# lpc134x.net
KiCad netlist of a schematic drawn in EAGLE
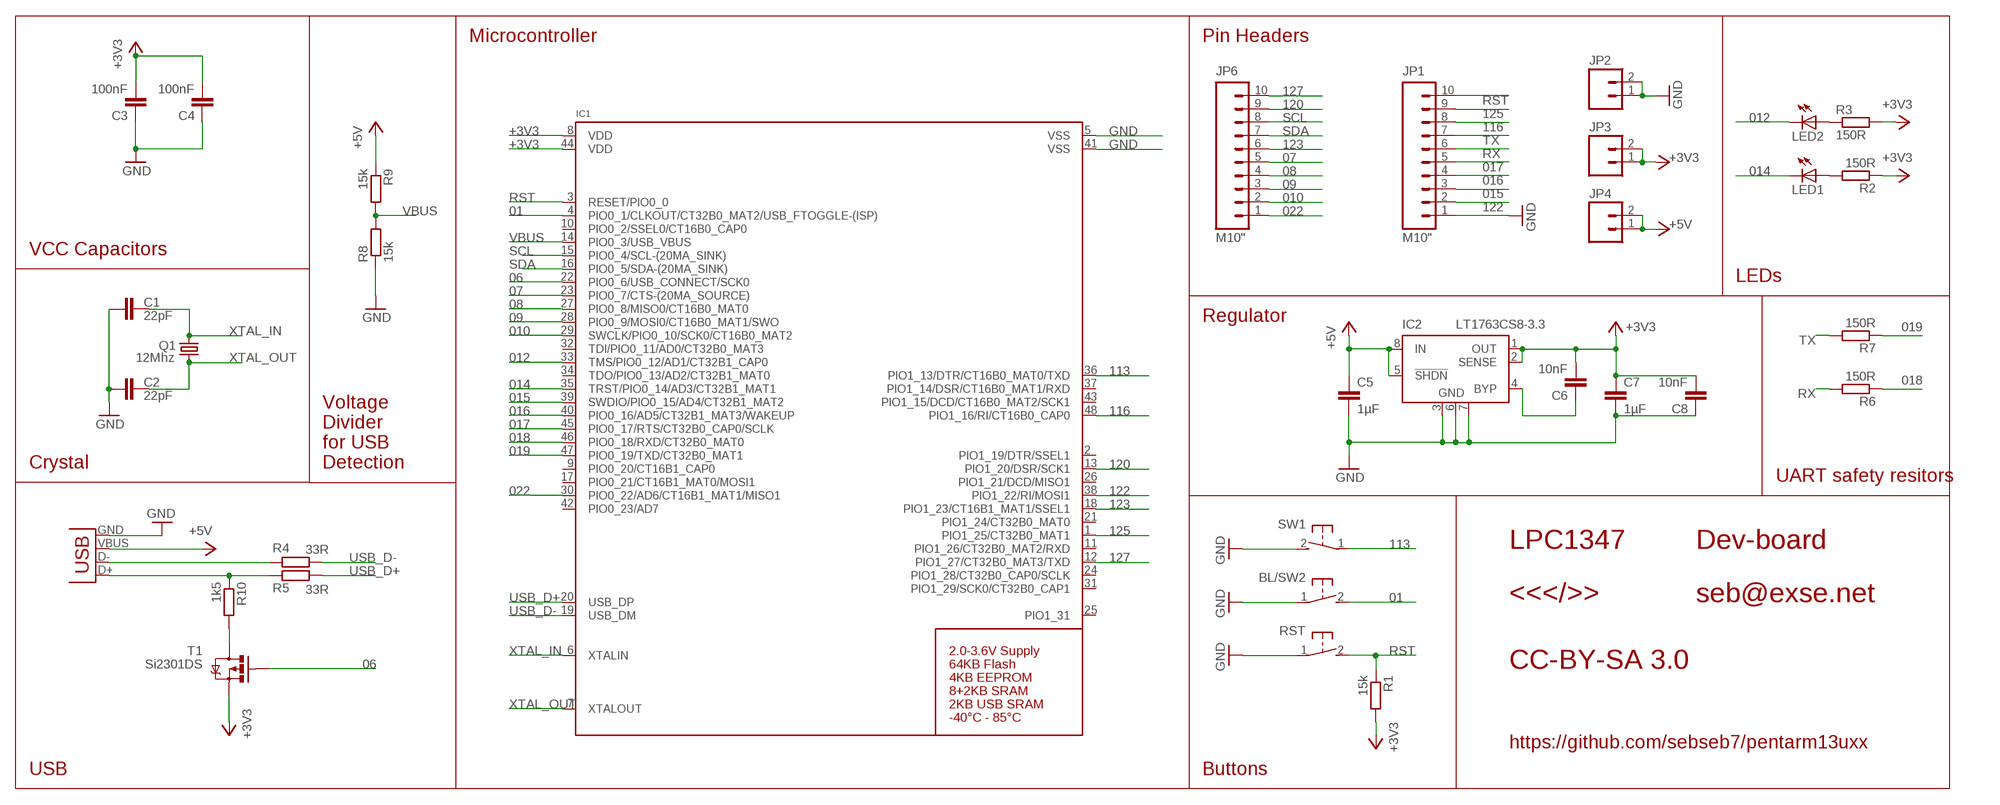
[diagram p0: schematic, sheet 1]

(export (version "E")
  (design (tool "Eeschema 10.0.6"))
  (components
    (comp (ref "BL/SW2")
      (value "SWITCH_MCTAEF")
      (footprint "eagle-import:SWITCH_MCTAEF")
      (libsource (lib "eagle-import") (part "SWITCH_MCTAEF"))
    )
    (comp (ref "C1")
      (value "22pF")
      (footprint "eagle-import:C0402")
      (libsource (lib "eagle-import") (part "C-EUC0402"))
    )
    (comp (ref "C2")
      (value "22pF")
      (footprint "eagle-import:C0402")
      (libsource (lib "eagle-import") (part "C-EUC0402"))
    )
    (comp (ref "C3")
      (value "100nF")
      (footprint "eagle-import:C0402")
      (libsource (lib "eagle-import") (part "C-EUC0402"))
    )
    (comp (ref "C4")
      (value "100nF")
      (footprint "eagle-import:C0402")
      (libsource (lib "eagle-import") (part "C-EUC0402"))
    )
    (comp (ref "C5")
      (value "1µF")
      (footprint "eagle-import:0805")
      (libsource (lib "eagle-import") (part "CAP0805"))
    )
    (comp (ref "C6")
      (value "10nF")
      (footprint "eagle-import:C0402")
      (libsource (lib "eagle-import") (part "C-EUC0402"))
    )
    (comp (ref "C7")
      (value "1µF")
      (footprint "eagle-import:0805")
      (libsource (lib "eagle-import") (part "CAP0805"))
    )
    (comp (ref "C8")
      (value "10nF")
      (footprint "eagle-import:C0402")
      (libsource (lib "eagle-import") (part "C-EUC0402"))
    )
    (comp (ref "IC1")
      (value "LPC1347_QFP48")
      (footprint "eagle-import:LQFP48")
      (libsource (lib "eagle-import") (part "LPC1347_QFP48"))
    )
    (comp (ref "IC2")
      (value "LT1763CS8-3.3")
      (footprint "eagle-import:SOIC8")
      (libsource (lib "eagle-import") (part "LT1763CS8-3.3"))
    )
    (comp (ref "JP1")
      (value "M10\"")
      (footprint "eagle-import:1X10")
      (libsource (lib "eagle-import") (part "M10{dblquote}"))
    )
    (comp (ref "JP2")
      (value "M02PTH")
      (footprint "eagle-import:1X02")
      (libsource (lib "eagle-import") (part "M02PTH"))
    )
    (comp (ref "JP3")
      (value "M02PTH")
      (footprint "eagle-import:1X02")
      (libsource (lib "eagle-import") (part "M02PTH"))
    )
    (comp (ref "JP4")
      (value "M02PTH")
      (footprint "eagle-import:1X02")
      (libsource (lib "eagle-import") (part "M02PTH"))
    )
    (comp (ref "JP6")
      (value "M10\"")
      (footprint "eagle-import:1X10")
      (libsource (lib "eagle-import") (part "M10{dblquote}"))
    )
    (comp (ref "LED1")
      (value "LEDCHIPLED_0805")
      (footprint "eagle-import:CHIPLED_0805")
      (libsource (lib "eagle-import") (part "LEDCHIPLED_0805"))
    )
    (comp (ref "LED2")
      (value "LEDCHIPLED_0805")
      (footprint "eagle-import:CHIPLED_0805")
      (libsource (lib "eagle-import") (part "LEDCHIPLED_0805"))
    )
    (comp (ref "Q1")
      (value "12Mhz")
      (footprint "eagle-import:MT")
      (libsource (lib "eagle-import") (part "MT-OSCILLATOR"))
    )
    (comp (ref "R1")
      (value "15k")
      (footprint "eagle-import:R0402")
      (libsource (lib "eagle-import") (part "R-EU_R0402"))
    )
    (comp (ref "R2")
      (value "150R")
      (footprint "eagle-import:R0402")
      (libsource (lib "eagle-import") (part "R-EU_R0402"))
    )
    (comp (ref "R3")
      (value "150R")
      (footprint "eagle-import:R0402")
      (libsource (lib "eagle-import") (part "R-EU_R0402"))
    )
    (comp (ref "R4")
      (value "33R")
      (footprint "eagle-import:R0402")
      (libsource (lib "eagle-import") (part "R-EU_R0402"))
    )
    (comp (ref "R5")
      (value "33R")
      (footprint "eagle-import:R0402")
      (libsource (lib "eagle-import") (part "R-EU_R0402"))
    )
    (comp (ref "R6")
      (value "150R")
      (footprint "eagle-import:R0402")
      (libsource (lib "eagle-import") (part "R-EU_R0402"))
    )
    (comp (ref "R7")
      (value "150R")
      (footprint "eagle-import:R0402")
      (libsource (lib "eagle-import") (part "R-EU_R0402"))
    )
    (comp (ref "R8")
      (value "15k")
      (footprint "eagle-import:R0402")
      (libsource (lib "eagle-import") (part "R-EU_R0402"))
    )
    (comp (ref "R9")
      (value "15k")
      (footprint "eagle-import:R0402")
      (libsource (lib "eagle-import") (part "R-EU_R0402"))
    )
    (comp (ref "R10")
      (value "1k5")
      (footprint "eagle-import:R0402")
      (libsource (lib "eagle-import") (part "R-EU_R0402"))
    )
    (comp (ref "RST")
      (value "SWITCH_MCTAEF")
      (footprint "eagle-import:SWITCH_MCTAEF")
      (libsource (lib "eagle-import") (part "SWITCH_MCTAEF"))
    )
    (comp (ref "SW1")
      (value "SWITCH_MCTAEF")
      (footprint "eagle-import:SWITCH_MCTAEF")
      (libsource (lib "eagle-import") (part "SWITCH_MCTAEF"))
    )
    (comp (ref "T1")
      (value "Si2301DS")
      (footprint "eagle-import:SOT23")
      (libsource (lib "eagle-import") (part "MOSFET-PCHANNEL"))
    )
    (comp (ref "X2")
      (value "USB-SMD-NS")
      (footprint "eagle-import:USB-MINIB-NOSTOP")
      (libsource (lib "eagle-import") (part "USB-SMD-NS"))
    )
  )
  (nets
    (net (code "1") (name "+3V3") (class "Default")
      (node (ref "C3") (pin "2") (pinfunction "2_2") (pintype "passive"))
      (node (ref "C4") (pin "2") (pinfunction "2_2") (pintype "passive"))
      (node (ref "C6") (pin "2") (pinfunction "2_2") (pintype "passive"))
      (node (ref "C7") (pin "1") (pinfunction "1_1") (pintype "passive"))
      (node (ref "C8") (pin "2") (pinfunction "2_2") (pintype "passive"))
      (node (ref "IC1") (pin "44") (pinfunction "VDD_44") (pintype "power_in"))
      (node (ref "IC1") (pin "8") (pinfunction "VDD_8") (pintype "power_in"))
      (node (ref "IC2") (pin "1") (pinfunction "OUT_1") (pintype "passive"))
      (node (ref "IC2") (pin "2") (pinfunction "SENSE_2") (pintype "input"))
      (node (ref "JP3") (pin "1") (pinfunction "1_1") (pintype "passive"))
      (node (ref "JP3") (pin "2") (pinfunction "2_2") (pintype "passive"))
      (node (ref "R1") (pin "2") (pinfunction "2_2") (pintype "passive"))
      (node (ref "R2") (pin "1") (pinfunction "1_1") (pintype "passive"))
      (node (ref "R3") (pin "2") (pinfunction "2_2") (pintype "passive"))
      (node (ref "T1") (pin "2") (pinfunction "S_2") (pintype "passive"))
    )
    (net (code "2") (name "+5V") (class "Default")
      (node (ref "C5") (pin "1") (pinfunction "1_1") (pintype "passive"))
      (node (ref "IC2") (pin "5") (pinfunction "~{SHDN}_5") (pintype "input"))
      (node (ref "IC2") (pin "8") (pinfunction "IN_8") (pintype "input"))
      (node (ref "JP4") (pin "1") (pinfunction "1_1") (pintype "passive"))
      (node (ref "JP4") (pin "2") (pinfunction "2_2") (pintype "passive"))
      (node (ref "R9") (pin "1") (pinfunction "1_1") (pintype "passive"))
      (node (ref "X2") (pin "VBUS") (pinfunction "VBUS_VBUS") (pintype "bidirectional"))
    )
    (net (code "3") (name "/01") (class "Default")
      (node (ref "BL/SW2") (pin "2") (pinfunction "2_2") (pintype "passive"))
      (node (ref "IC1") (pin "4") (pinfunction "PIO0_1/CLKOUT/CT32B0_MAT2/USB_FTOGGLE-(ISP)_4") (pintype "bidirectional"))
    )
    (net (code "4") (name "/06") (class "Default")
      (node (ref "IC1") (pin "22") (pinfunction "PIO0_6/USB_CONNECT/SCK0_22") (pintype "bidirectional"))
      (node (ref "T1") (pin "1") (pinfunction "G_1") (pintype "passive"))
    )
    (net (code "5") (name "/07") (class "Default")
      (node (ref "IC1") (pin "23") (pinfunction "PIO0_7/CTS-(20MA_SOURCE)_23") (pintype "bidirectional"))
      (node (ref "JP6") (pin "5") (pinfunction "5_5") (pintype "passive"))
    )
    (net (code "6") (name "/08") (class "Default")
      (node (ref "IC1") (pin "27") (pinfunction "PIO0_8/MISO0/CT16B0_MAT0_27") (pintype "bidirectional"))
      (node (ref "JP6") (pin "4") (pinfunction "4_4") (pintype "passive"))
    )
    (net (code "7") (name "/09") (class "Default")
      (node (ref "IC1") (pin "28") (pinfunction "PIO0_9/MOSI0/CT16B0_MAT1/SWO_28") (pintype "bidirectional"))
      (node (ref "JP6") (pin "3") (pinfunction "3_3") (pintype "passive"))
    )
    (net (code "8") (name "/010") (class "Default")
      (node (ref "IC1") (pin "29") (pinfunction "SWCLK/PIO0_10/SCK0/CT16B0_MAT2_29") (pintype "bidirectional"))
      (node (ref "JP6") (pin "2") (pinfunction "2_2") (pintype "passive"))
    )
    (net (code "9") (name "/012") (class "Default")
      (node (ref "IC1") (pin "33") (pinfunction "TMS/PIO0_12/AD1/CT32B1_CAP0_33") (pintype "bidirectional"))
      (node (ref "LED2") (pin "C") (pinfunction "C_C") (pintype "passive"))
    )
    (net (code "10") (name "/014") (class "Default")
      (node (ref "IC1") (pin "35") (pinfunction "TRST/PIO0_14/AD3/CT32B1_MAT1_35") (pintype "bidirectional"))
      (node (ref "LED1") (pin "C") (pinfunction "C_C") (pintype "passive"))
    )
    (net (code "11") (name "/015") (class "Default")
      (node (ref "IC1") (pin "39") (pinfunction "SWDIO/PIO0_15/AD4/CT32B1_MAT2_39") (pintype "bidirectional"))
      (node (ref "JP1") (pin "3") (pinfunction "3_3") (pintype "passive"))
    )
    (net (code "12") (name "/016") (class "Default")
      (node (ref "IC1") (pin "40") (pinfunction "PIO0_16/AD5/CT32B1_MAT3/WAKEUP_40") (pintype "bidirectional"))
      (node (ref "JP1") (pin "4") (pinfunction "4_4") (pintype "passive"))
    )
    (net (code "13") (name "/017") (class "Default")
      (node (ref "IC1") (pin "45") (pinfunction "PIO0_17/RTS/CT32B0_CAP0/SCLK_45") (pintype "bidirectional"))
      (node (ref "JP1") (pin "5") (pinfunction "5_5") (pintype "passive"))
    )
    (net (code "14") (name "/018") (class "Default")
      (node (ref "IC1") (pin "46") (pinfunction "PIO0_18/RXD/CT32B0_MAT0_46") (pintype "bidirectional"))
      (node (ref "R6") (pin "1") (pinfunction "1_1") (pintype "passive"))
    )
    (net (code "15") (name "/019") (class "Default")
      (node (ref "IC1") (pin "47") (pinfunction "PIO0_19/TXD/CT32B0_MAT1_47") (pintype "bidirectional"))
      (node (ref "R7") (pin "1") (pinfunction "1_1") (pintype "passive"))
    )
    (net (code "16") (name "/022") (class "Default")
      (node (ref "IC1") (pin "30") (pinfunction "PIO0_22/AD6/CT16B1_MAT1/MISO1_30") (pintype "bidirectional"))
      (node (ref "JP6") (pin "1") (pinfunction "1_1") (pintype "passive"))
    )
    (net (code "17") (name "/113") (class "Default")
      (node (ref "IC1") (pin "36") (pinfunction "PIO1_13/DTR/CT16B0_MAT0/TXD_36") (pintype "bidirectional"))
      (node (ref "SW1") (pin "1") (pinfunction "1_1") (pintype "passive"))
    )
    (net (code "18") (name "/116") (class "Default")
      (node (ref "IC1") (pin "48") (pinfunction "PIO1_16/RI/CT16B0_CAP0_48") (pintype "bidirectional"))
      (node (ref "JP1") (pin "8") (pinfunction "8_8") (pintype "passive"))
    )
    (net (code "19") (name "/120") (class "Default")
      (node (ref "IC1") (pin "13") (pinfunction "PIO1_20/DSR/SCK1_13") (pintype "bidirectional"))
      (node (ref "JP6") (pin "9") (pinfunction "9_9") (pintype "passive"))
    )
    (net (code "20") (name "/122") (class "Default")
      (node (ref "IC1") (pin "38") (pinfunction "PIO1_22/RI/MOSI1_38") (pintype "bidirectional"))
      (node (ref "JP1") (pin "2") (pinfunction "2_2") (pintype "passive"))
    )
    (net (code "21") (name "/123") (class "Default")
      (node (ref "IC1") (pin "18") (pinfunction "PIO1_23/CT16B1_MAT1/SSEL1_18") (pintype "bidirectional"))
      (node (ref "JP6") (pin "6") (pinfunction "6_6") (pintype "passive"))
    )
    (net (code "22") (name "/125") (class "Default")
      (node (ref "IC1") (pin "1") (pinfunction "PIO1_25/CT32B0_MAT1_1") (pintype "bidirectional"))
      (node (ref "JP1") (pin "9") (pinfunction "9_9") (pintype "passive"))
    )
    (net (code "23") (name "/127") (class "Default")
      (node (ref "IC1") (pin "12") (pinfunction "PIO1_27/CT32B0_MAT3/TXD_12") (pintype "bidirectional"))
      (node (ref "JP6") (pin "10") (pinfunction "10_10") (pintype "passive"))
    )
    (net (code "24") (name "/RST") (class "Default")
      (node (ref "IC1") (pin "3") (pinfunction "RESET/PIO0_0_3") (pintype "bidirectional"))
      (node (ref "JP1") (pin "10") (pinfunction "10_10") (pintype "passive"))
      (node (ref "R1") (pin "1") (pinfunction "1_1") (pintype "passive"))
      (node (ref "RST") (pin "2") (pinfunction "2_2") (pintype "passive"))
    )
    (net (code "25") (name "/RX") (class "Default")
      (node (ref "JP1") (pin "6") (pinfunction "6_6") (pintype "passive"))
      (node (ref "R6") (pin "2") (pinfunction "2_2") (pintype "passive"))
    )
    (net (code "26") (name "/SCL") (class "Default")
      (node (ref "IC1") (pin "15") (pinfunction "PIO0_4/SCL-(20MA_SINK)_15") (pintype "bidirectional"))
      (node (ref "JP6") (pin "8") (pinfunction "8_8") (pintype "passive"))
    )
    (net (code "27") (name "/SDA") (class "Default")
      (node (ref "IC1") (pin "16") (pinfunction "PIO0_5/SDA-(20MA_SINK)_16") (pintype "bidirectional"))
      (node (ref "JP6") (pin "7") (pinfunction "7_7") (pintype "passive"))
    )
    (net (code "28") (name "/TX") (class "Default")
      (node (ref "JP1") (pin "7") (pinfunction "7_7") (pintype "passive"))
      (node (ref "R7") (pin "2") (pinfunction "2_2") (pintype "passive"))
    )
    (net (code "29") (name "/USB_D+") (class "Default")
      (node (ref "IC1") (pin "20") (pinfunction "USB_DP_20") (pintype "bidirectional"))
      (node (ref "R5") (pin "1") (pinfunction "1_1") (pintype "passive"))
    )
    (net (code "30") (name "/USB_D-") (class "Default")
      (node (ref "IC1") (pin "19") (pinfunction "USB_DM_19") (pintype "bidirectional"))
      (node (ref "R4") (pin "1") (pinfunction "1_1") (pintype "passive"))
    )
    (net (code "31") (name "/VBUS") (class "Default")
      (node (ref "IC1") (pin "14") (pinfunction "PIO0_3/USB_VBUS_14") (pintype "bidirectional"))
      (node (ref "R8") (pin "2") (pinfunction "2_2") (pintype "passive"))
      (node (ref "R9") (pin "2") (pinfunction "2_2") (pintype "passive"))
    )
    (net (code "32") (name "/XTAL_IN") (class "Default")
      (node (ref "C1") (pin "2") (pinfunction "2_2") (pintype "passive"))
      (node (ref "IC1") (pin "6") (pinfunction "XTALIN_6") (pintype "bidirectional"))
      (node (ref "Q1") (pin "3") (pinfunction "2_3") (pintype "passive"))
    )
    (net (code "33") (name "/XTAL_OUT") (class "Default")
      (node (ref "C2") (pin "2") (pinfunction "2_2") (pintype "passive"))
      (node (ref "IC1") (pin "7") (pinfunction "XTALOUT_7") (pintype "bidirectional"))
      (node (ref "Q1") (pin "1") (pinfunction "1_1") (pintype "passive"))
    )
    (net (code "34") (name "GND") (class "Default")
      (node (ref "BL/SW2") (pin "1") (pinfunction "1_1") (pintype "passive"))
      (node (ref "C1") (pin "1") (pinfunction "1_1") (pintype "passive"))
      (node (ref "C2") (pin "1") (pinfunction "1_1") (pintype "passive"))
      (node (ref "C3") (pin "1") (pinfunction "1_1") (pintype "passive"))
      (node (ref "C4") (pin "1") (pinfunction "1_1") (pintype "passive"))
      (node (ref "C5") (pin "2") (pinfunction "2_2") (pintype "passive"))
      (node (ref "C7") (pin "2") (pinfunction "2_2") (pintype "passive"))
      (node (ref "C8") (pin "1") (pinfunction "1_1") (pintype "passive"))
      (node (ref "IC1") (pin "41") (pinfunction "VSS_41") (pintype "power_in"))
      (node (ref "IC1") (pin "5") (pinfunction "VSS_5") (pintype "power_in"))
      (node (ref "IC2") (pin "3") (pinfunction "GND_3") (pintype "power_in"))
      (node (ref "IC2") (pin "6") (pinfunction "GND_6") (pintype "power_in"))
      (node (ref "IC2") (pin "7") (pinfunction "GND_7") (pintype "power_in"))
      (node (ref "JP1") (pin "1") (pinfunction "1_1") (pintype "passive"))
      (node (ref "JP2") (pin "1") (pinfunction "1_1") (pintype "passive"))
      (node (ref "JP2") (pin "2") (pinfunction "2_2") (pintype "passive"))
      (node (ref "R8") (pin "1") (pinfunction "1_1") (pintype "passive"))
      (node (ref "RST") (pin "1") (pinfunction "1_1") (pintype "passive"))
      (node (ref "SW1") (pin "2") (pinfunction "2_2") (pintype "passive"))
      (node (ref "X2") (pin "GND") (pinfunction "GND_GND") (pintype "bidirectional"))
    )
    (net (code "35") (name "Net-(IC2-BYP)") (class "Default")
      (node (ref "C6") (pin "1") (pinfunction "1_1") (pintype "passive"))
      (node (ref "IC2") (pin "4") (pinfunction "BYP_4") (pintype "input"))
    )
    (net (code "36") (name "Net-(LED1-PadA)") (class "Default")
      (node (ref "LED1") (pin "A") (pinfunction "A_A") (pintype "passive"))
      (node (ref "R2") (pin "2") (pinfunction "2_2") (pintype "passive"))
    )
    (net (code "37") (name "Net-(LED2-PadA)") (class "Default")
      (node (ref "LED2") (pin "A") (pinfunction "A_A") (pintype "passive"))
      (node (ref "R3") (pin "1") (pinfunction "1_1") (pintype "passive"))
    )
    (net (code "38") (name "Net-(R4-Pad2)") (class "Default")
      (node (ref "R4") (pin "2") (pinfunction "2_2") (pintype "passive"))
      (node (ref "X2") (pin "D-") (pinfunction "D-_D-") (pintype "bidirectional"))
    )
    (net (code "39") (name "Net-(R10-Pad1)") (class "Default")
      (node (ref "R10") (pin "1") (pinfunction "1_1") (pintype "passive"))
      (node (ref "R5") (pin "2") (pinfunction "2_2") (pintype "passive"))
      (node (ref "X2") (pin "D+") (pinfunction "D+_D+") (pintype "bidirectional"))
    )
    (net (code "40") (name "Net-(T1-D)") (class "Default")
      (node (ref "R10") (pin "2") (pinfunction "2_2") (pintype "passive"))
      (node (ref "T1") (pin "3") (pinfunction "D_3") (pintype "passive"))
    )
    (net (code "41") (name "unconnected-(IC1-PIO0_2{slash}SSEL0{slash}CT16B0_CAP0-Pad10)") (class "Default")
      (node (ref "IC1") (pin "10") (pinfunction "PIO0_2/SSEL0/CT16B0_CAP0_10") (pintype "bidirectional"))
    )
    (net (code "42") (name "unconnected-(IC1-PIO0_20{slash}CT16B1_CAP0-Pad9)") (class "Default")
      (node (ref "IC1") (pin "9") (pinfunction "PIO0_20/CT16B1_CAP0_9") (pintype "bidirectional"))
    )
    (net (code "43") (name "unconnected-(IC1-PIO0_21{slash}CT16B1_MAT0{slash}MOSI1-Pad17)") (class "Default")
      (node (ref "IC1") (pin "17") (pinfunction "PIO0_21/CT16B1_MAT0/MOSI1_17") (pintype "bidirectional"))
    )
    (net (code "44") (name "unconnected-(IC1-PIO0_23{slash}AD7-Pad42)") (class "Default")
      (node (ref "IC1") (pin "42") (pinfunction "PIO0_23/AD7_42") (pintype "bidirectional"))
    )
    (net (code "45") (name "unconnected-(IC1-PIO1_14{slash}DSR{slash}CT16B0_MAT1{slash}RXD-Pad37)") (class "Default")
      (node (ref "IC1") (pin "37") (pinfunction "PIO1_14/DSR/CT16B0_MAT1/RXD_37") (pintype "bidirectional"))
    )
    (net (code "46") (name "unconnected-(IC1-PIO1_15{slash}DCD{slash}CT16B0_MAT2{slash}SCK1-Pad43)") (class "Default")
      (node (ref "IC1") (pin "43") (pinfunction "PIO1_15/DCD/CT16B0_MAT2/SCK1_43") (pintype "bidirectional"))
    )
    (net (code "47") (name "unconnected-(IC1-PIO1_19{slash}DTR{slash}SSEL1-Pad2)") (class "Default")
      (node (ref "IC1") (pin "2") (pinfunction "PIO1_19/DTR/SSEL1_2") (pintype "bidirectional"))
    )
    (net (code "48") (name "unconnected-(IC1-PIO1_21{slash}DCD{slash}MISO1-Pad26)") (class "Default")
      (node (ref "IC1") (pin "26") (pinfunction "PIO1_21/DCD/MISO1_26") (pintype "bidirectional"))
    )
    (net (code "49") (name "unconnected-(IC1-PIO1_24{slash}CT32B0_MAT0-Pad21)") (class "Default")
      (node (ref "IC1") (pin "21") (pinfunction "PIO1_24/CT32B0_MAT0_21") (pintype "bidirectional"))
    )
    (net (code "50") (name "unconnected-(IC1-PIO1_26{slash}CT32B0_MAT2{slash}RXD-Pad11)") (class "Default")
      (node (ref "IC1") (pin "11") (pinfunction "PIO1_26/CT32B0_MAT2/RXD_11") (pintype "bidirectional"))
    )
    (net (code "51") (name "unconnected-(IC1-PIO1_28{slash}CT32B0_CAP0{slash}SCLK-Pad24)") (class "Default")
      (node (ref "IC1") (pin "24") (pinfunction "PIO1_28/CT32B0_CAP0/SCLK_24") (pintype "bidirectional"))
    )
    (net (code "52") (name "unconnected-(IC1-PIO1_29{slash}SCK0{slash}CT32B0_CAP1-Pad31)") (class "Default")
      (node (ref "IC1") (pin "31") (pinfunction "PIO1_29/SCK0/CT32B0_CAP1_31") (pintype "bidirectional"))
    )
    (net (code "53") (name "unconnected-(IC1-PIO1_31-Pad25)") (class "Default")
      (node (ref "IC1") (pin "25") (pinfunction "PIO1_31_25") (pintype "bidirectional"))
    )
    (net (code "54") (name "unconnected-(IC1-TDI{slash}PIO0_11{slash}AD0{slash}CT32B0_MAT3-Pad32)") (class "Default")
      (node (ref "IC1") (pin "32") (pinfunction "TDI/PIO0_11/AD0/CT32B0_MAT3_32") (pintype "bidirectional"))
    )
    (net (code "55") (name "unconnected-(IC1-TDO{slash}PIO0_13{slash}AD2{slash}CT32B1_MAT0-Pad34)") (class "Default")
      (node (ref "IC1") (pin "34") (pinfunction "TDO/PIO0_13/AD2/CT32B1_MAT0_34") (pintype "bidirectional"))
    )
  )
)
